# SingEndOutput.net
KiCad netlist of a schematic drawn in Altium Designer
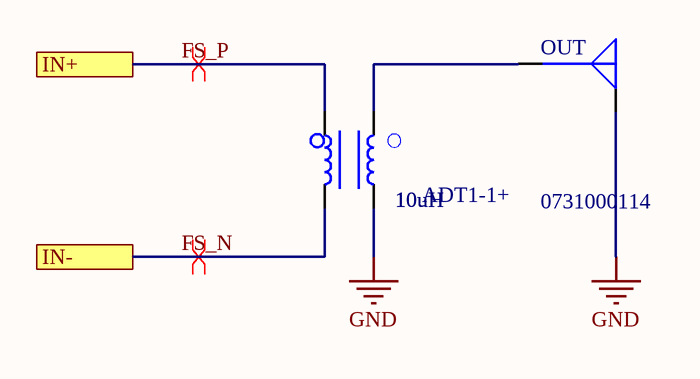
[diagram p0: SingEndOutput.SchDoc]

(export (version "E")
  (design (tool "Eeschema 10.0.6"))
  (components
    (comp (ref "OUT")
      (value "0731000114")
      (footprint "MOLEX SD-73100-0114")
      (description "CONN SMA RCPT R/A 50 OHM PCB")
      (fields (field (name "MANUFACTURER") "Molex"))
      (libsource (lib "Celestial Library Database") (part "RF Connector - SMA"))
    )
    (comp (ref "XRF")
      (value "ADT1-1+")
      (footprint "ADT1-1+")
      (description "RF XFMR 50Ohm / SURF MOUNT / RoHS")
      (fields
        (field (name "MANUFACTURER") "Mini-Circuits")
        (field (name "INDUCTANCE A") "10uH")
        (field (name "INDUCTANCE B") "10uH")
        (field (name "COUPLING FACTOR") "1")
      )
      (libsource (lib "Celestial Library Database") (part "ADT1-1+"))
    )
  )
  (nets
    (net (code "1") (name "/FS_N") (class "Default")
      (node (ref "XRF") (pin "1") (pinfunction "1_1") (pintype "passive"))
    )
    (net (code "2") (name "/FS_P") (class "Default")
      (node (ref "XRF") (pin "3") (pinfunction "3_3") (pintype "passive"))
    )
    (net (code "3") (name "GND") (class "Default")
      (node (ref "OUT") (pin "G") (pinfunction "G_G") (pintype "passive"))
      (node (ref "XRF") (pin "6") (pinfunction "1_6") (pintype "passive"))
    )
    (net (code "4") (name "Net-(XRF-2)") (class "Default")
      (node (ref "OUT") (pin "S") (pinfunction "S_S") (pintype "passive"))
      (node (ref "XRF") (pin "4") (pinfunction "2_4") (pintype "passive"))
    )
  )
)
